# Relays.net
KiCad netlist of a schematic drawn in Altium Designer
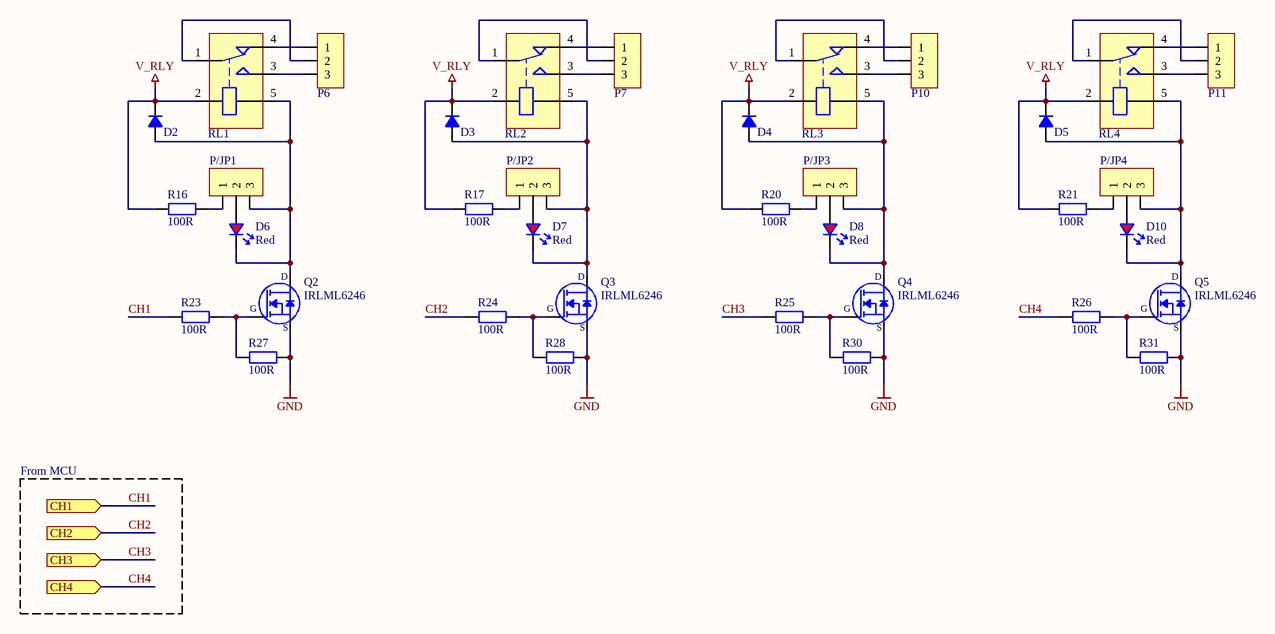
[diagram p0: Relays.SchDoc]

(export (version "E")
  (design (tool "Eeschema 10.0.6"))
  (components
    (comp (ref "D2")
      (value "D_SM")
      (footprint "AG.Passive:DO-214AC")
      (description "Generic Diode (Rectifier)")
      (libsource (lib "AG.Generic") (part "D_SM"))
    )
    (comp (ref "D3")
      (value "D_SM")
      (footprint "AG.Passive:DO-214AC")
      (description "Generic Diode (Rectifier)")
      (libsource (lib "AG.Generic") (part "D_SM"))
    )
    (comp (ref "D4")
      (value "D_SM")
      (footprint "AG.Passive:DO-214AC")
      (description "Generic Diode (Rectifier)")
      (libsource (lib "AG.Generic") (part "D_SM"))
    )
    (comp (ref "D5")
      (value "D_SM")
      (footprint "AG.Passive:DO-214AC")
      (description "Generic Diode (Rectifier)")
      (libsource (lib "AG.Generic") (part "D_SM"))
    )
    (comp (ref "D6")
      (value "Red")
      (footprint "AG.LED:LED1206")
      (description "Generic LED (Red)")
      (libsource (lib "AG.LED") (part "LED_RED"))
    )
    (comp (ref "D7")
      (value "Red")
      (footprint "AG.LED:LED1206")
      (description "Generic LED (Red)")
      (libsource (lib "AG.LED") (part "LED_RED"))
    )
    (comp (ref "D8")
      (value "Red")
      (footprint "AG.LED:LED1206")
      (description "Generic LED (Red)")
      (libsource (lib "AG.LED") (part "LED_RED"))
    )
    (comp (ref "D10")
      (value "Red")
      (footprint "AG.LED:LED1206")
      (description "Generic LED (Red)")
      (libsource (lib "AG.LED") (part "LED_RED"))
    )
    (comp (ref "P/JP1")
      (value "PINHDR_3x1")
      (footprint "AG.Connectors:HEADER-2.54-3P1")
      (description "Generic Pin Header 3x1")
      (libsource (lib "AG.Connectors") (part "PINHDR_3x1"))
    )
    (comp (ref "P/JP2")
      (value "PINHDR_3x1")
      (footprint "AG.Connectors:HEADER-2.54-3P1")
      (description "Generic Pin Header 3x1")
      (libsource (lib "AG.Connectors") (part "PINHDR_3x1"))
    )
    (comp (ref "P/JP3")
      (value "PINHDR_3x1")
      (footprint "AG.Connectors:HEADER-2.54-3P1")
      (description "Generic Pin Header 3x1")
      (libsource (lib "AG.Connectors") (part "PINHDR_3x1"))
    )
    (comp (ref "P/JP4")
      (value "PINHDR_3x1")
      (footprint "AG.Connectors:HEADER-2.54-3P1")
      (description "Generic Pin Header 3x1")
      (libsource (lib "AG.Connectors") (part "PINHDR_3x1"))
    )
    (comp (ref "P6")
      (value "ED500XDS-3")
      (footprint "AG.Connectors:ED500XDS-3")
      (description "TERM BLK 3P SIDE ENT 5.08MM PCB")
      (fields (field (name "PART NO") "EDZ500/3DS") (field (name "VOLTAGE") "300V"))
      (libsource (lib "AG.Connectors") (part "ED500XDS-3"))
    )
    (comp (ref "P7")
      (value "ED500XDS-3")
      (footprint "AG.Connectors:ED500XDS-3")
      (description "TERM BLK 3P SIDE ENT 5.08MM PCB")
      (fields (field (name "PART NO") "EDZ500/3DS") (field (name "VOLTAGE") "300V"))
      (libsource (lib "AG.Connectors") (part "ED500XDS-3"))
    )
    (comp (ref "P10")
      (value "ED500XDS-3")
      (footprint "AG.Connectors:ED500XDS-3")
      (description "TERM BLK 3P SIDE ENT 5.08MM PCB")
      (fields (field (name "PART NO") "EDZ500/3DS") (field (name "VOLTAGE") "300V"))
      (libsource (lib "AG.Connectors") (part "ED500XDS-3"))
    )
    (comp (ref "P11")
      (value "ED500XDS-3")
      (footprint "AG.Connectors:ED500XDS-3")
      (description "TERM BLK 3P SIDE ENT 5.08MM PCB")
      (fields (field (name "PART NO") "EDZ500/3DS") (field (name "VOLTAGE") "300V"))
      (libsource (lib "AG.Connectors") (part "ED500XDS-3"))
    )
    (comp (ref "Q2")
      (value "IRLML6246")
      (footprint "SOT-23-127P600-8N")
      (description "MOSFET N-CH 20V 4.1A SOT-23")
      (fields
        (field (name "PARTNO") "IRLML6246TRPBFCT-ND")
        (field (name "MANUFACTURER") "Infineon Technologies")
      )
      (libsource (lib "AG") (part "IRLML6246TRPBF"))
    )
    (comp (ref "Q3")
      (value "IRLML6246")
      (footprint "SOT-23-127P600-8N")
      (description "MOSFET N-CH 20V 4.1A SOT-23")
      (fields
        (field (name "PARTNO") "IRLML6246TRPBFCT-ND")
        (field (name "MANUFACTURER") "Infineon Technologies")
      )
      (libsource (lib "AG") (part "IRLML6246TRPBF"))
    )
    (comp (ref "Q4")
      (value "IRLML6246")
      (footprint "SOT-23-127P600-8N")
      (description "MOSFET N-CH 20V 4.1A SOT-23")
      (fields
        (field (name "PARTNO") "IRLML6246TRPBFCT-ND")
        (field (name "MANUFACTURER") "Infineon Technologies")
      )
      (libsource (lib "AG") (part "IRLML6246TRPBF"))
    )
    (comp (ref "Q5")
      (value "IRLML6246")
      (footprint "SOT-23-127P600-8N")
      (description "MOSFET N-CH 20V 4.1A SOT-23")
      (fields
        (field (name "PARTNO") "IRLML6246TRPBFCT-ND")
        (field (name "MANUFACTURER") "Infineon Technologies")
      )
      (libsource (lib "AG") (part "IRLML6246TRPBF"))
    )
    (comp (ref "R16")
      (value "100R")
      (footprint "AG.Passive:R0805")
      (description "Generic Resistor")
      (fields (field (name "TOLERANCE") "1%"))
      (libsource (lib "AG.Generic") (part "R"))
    )
    (comp (ref "R17")
      (value "100R")
      (footprint "AG.Passive:R0805")
      (description "Generic Resistor")
      (fields (field (name "TOLERANCE") "1%"))
      (libsource (lib "AG.Generic") (part "R"))
    )
    (comp (ref "R20")
      (value "100R")
      (footprint "AG.Passive:R0805")
      (description "Generic Resistor")
      (fields (field (name "TOLERANCE") "1%"))
      (libsource (lib "AG.Generic") (part "R"))
    )
    (comp (ref "R21")
      (value "100R")
      (footprint "AG.Passive:R0805")
      (description "Generic Resistor")
      (fields (field (name "TOLERANCE") "1%"))
      (libsource (lib "AG.Generic") (part "R"))
    )
    (comp (ref "R23")
      (value "100R")
      (footprint "AG.Passive:R0805")
      (description "Generic Resistor")
      (fields (field (name "TOLERANCE") "1%"))
      (libsource (lib "AG.Generic") (part "R"))
    )
    (comp (ref "R24")
      (value "100R")
      (footprint "AG.Passive:R0805")
      (description "Generic Resistor")
      (fields (field (name "TOLERANCE") "1%"))
      (libsource (lib "AG.Generic") (part "R"))
    )
    (comp (ref "R25")
      (value "100R")
      (footprint "AG.Passive:R0805")
      (description "Generic Resistor")
      (fields (field (name "TOLERANCE") "1%"))
      (libsource (lib "AG.Generic") (part "R"))
    )
    (comp (ref "R26")
      (value "100R")
      (footprint "AG.Passive:R0805")
      (description "Generic Resistor")
      (fields (field (name "TOLERANCE") "1%"))
      (libsource (lib "AG.Generic") (part "R"))
    )
    (comp (ref "R27")
      (value "100R")
      (footprint "AG.Passive:R0805")
      (description "Generic Resistor")
      (fields (field (name "TOLERANCE") "1%"))
      (libsource (lib "AG.Generic") (part "R"))
    )
    (comp (ref "R28")
      (value "100R")
      (footprint "AG.Passive:R0805")
      (description "Generic Resistor")
      (fields (field (name "TOLERANCE") "1%"))
      (libsource (lib "AG.Generic") (part "R"))
    )
    (comp (ref "R30")
      (value "100R")
      (footprint "AG.Passive:R0805")
      (description "Generic Resistor")
      (fields (field (name "TOLERANCE") "1%"))
      (libsource (lib "AG.Generic") (part "R"))
    )
    (comp (ref "R31")
      (value "100R")
      (footprint "AG.Passive:R0805")
      (description "Generic Resistor")
      (fields (field (name "TOLERANCE") "1%"))
      (libsource (lib "AG.Generic") (part "R"))
    )
    (comp (ref "RL1")
      (value "*")
      (footprint "AG.Relays:SRD-VDC-SL-C")
      (description "General Purpose Power Relay SPDT (1 Form C)")
      (libsource (lib "AG.Misc") (part "RELAY-SPDT"))
    )
    (comp (ref "RL2")
      (value "*")
      (footprint "AG.Relays:SRD-VDC-SL-C")
      (description "General Purpose Power Relay SPDT (1 Form C)")
      (libsource (lib "AG.Misc") (part "RELAY-SPDT"))
    )
    (comp (ref "RL3")
      (value "*")
      (footprint "AG.Relays:SRD-VDC-SL-C")
      (description "General Purpose Power Relay SPDT (1 Form C)")
      (libsource (lib "AG.Misc") (part "RELAY-SPDT"))
    )
    (comp (ref "RL4")
      (value "*")
      (footprint "AG.Relays:SRD-VDC-SL-C")
      (description "General Purpose Power Relay SPDT (1 Form C)")
      (libsource (lib "AG.Misc") (part "RELAY-SPDT"))
    )
  )
  (nets
    (net (code "1") (name "/CH1") (class "Default") (node (ref "R23") (pin "2") (pintype "passive")))
    (net (code "2") (name "/CH2") (class "Default") (node (ref "R24") (pin "2") (pintype "passive")))
    (net (code "3") (name "/CH3") (class "Default") (node (ref "R25") (pin "2") (pintype "passive")))
    (net (code "4") (name "/CH4") (class "Default") (node (ref "R26") (pin "2") (pintype "passive")))
    (net (code "5") (name "GND") (class "Default")
      (node (ref "Q2") (pin "2") (pinfunction "S_2") (pintype "passive"))
      (node (ref "Q3") (pin "2") (pinfunction "S_2") (pintype "passive"))
      (node (ref "Q4") (pin "2") (pinfunction "S_2") (pintype "passive"))
      (node (ref "Q5") (pin "2") (pinfunction "S_2") (pintype "passive"))
      (node (ref "R27") (pin "1") (pintype "passive"))
      (node (ref "R28") (pin "1") (pintype "passive"))
      (node (ref "R30") (pin "1") (pintype "passive"))
      (node (ref "R31") (pin "1") (pintype "passive"))
    )
    (net (code "6") (name "Net-(D2-A)") (class "Default")
      (node (ref "D2") (pin "1") (pinfunction "A_1") (pintype "passive"))
      (node (ref "D6") (pin "2") (pinfunction "C_2") (pintype "passive"))
      (node (ref "P/JP1") (pin "3") (pinfunction "3_3") (pintype "passive"))
      (node (ref "Q2") (pin "3") (pinfunction "D_3") (pintype "passive"))
      (node (ref "RL1") (pin "5") (pinfunction "SW1_5") (pintype "passive"))
    )
    (net (code "7") (name "Net-(D3-A)") (class "Default")
      (node (ref "D3") (pin "1") (pinfunction "A_1") (pintype "passive"))
      (node (ref "D7") (pin "2") (pinfunction "C_2") (pintype "passive"))
      (node (ref "P/JP2") (pin "3") (pinfunction "3_3") (pintype "passive"))
      (node (ref "Q3") (pin "3") (pinfunction "D_3") (pintype "passive"))
      (node (ref "RL2") (pin "5") (pinfunction "SW1_5") (pintype "passive"))
    )
    (net (code "8") (name "Net-(D4-A)") (class "Default")
      (node (ref "D4") (pin "1") (pinfunction "A_1") (pintype "passive"))
      (node (ref "D8") (pin "2") (pinfunction "C_2") (pintype "passive"))
      (node (ref "P/JP3") (pin "3") (pinfunction "3_3") (pintype "passive"))
      (node (ref "Q4") (pin "3") (pinfunction "D_3") (pintype "passive"))
      (node (ref "RL3") (pin "5") (pinfunction "SW1_5") (pintype "passive"))
    )
    (net (code "9") (name "Net-(D6-A)") (class "Default")
      (node (ref "D6") (pin "1") (pinfunction "A_1") (pintype "passive"))
      (node (ref "P/JP1") (pin "2") (pinfunction "2_2") (pintype "passive"))
    )
    (net (code "10") (name "Net-(D7-A)") (class "Default")
      (node (ref "D7") (pin "1") (pinfunction "A_1") (pintype "passive"))
      (node (ref "P/JP2") (pin "2") (pinfunction "2_2") (pintype "passive"))
    )
    (net (code "11") (name "Net-(D8-A)") (class "Default")
      (node (ref "D8") (pin "1") (pinfunction "A_1") (pintype "passive"))
      (node (ref "P/JP3") (pin "2") (pinfunction "2_2") (pintype "passive"))
    )
    (net (code "12") (name "Net-(D10-A)") (class "Default")
      (node (ref "D10") (pin "1") (pinfunction "A_1") (pintype "passive"))
      (node (ref "P/JP4") (pin "2") (pinfunction "2_2") (pintype "passive"))
    )
    (net (code "13") (name "Net-(D10-C)") (class "Default")
      (node (ref "D10") (pin "2") (pinfunction "C_2") (pintype "passive"))
      (node (ref "D5") (pin "1") (pinfunction "A_1") (pintype "passive"))
      (node (ref "P/JP4") (pin "3") (pinfunction "3_3") (pintype "passive"))
      (node (ref "Q5") (pin "3") (pinfunction "D_3") (pintype "passive"))
      (node (ref "RL4") (pin "5") (pinfunction "SW1_5") (pintype "passive"))
    )
    (net (code "14") (name "Net-(P/JP1-Pad1)") (class "Default")
      (node (ref "P/JP1") (pin "1") (pinfunction "1_1") (pintype "passive"))
      (node (ref "R16") (pin "1") (pintype "passive"))
    )
    (net (code "15") (name "Net-(P/JP2-Pad1)") (class "Default")
      (node (ref "P/JP2") (pin "1") (pinfunction "1_1") (pintype "passive"))
      (node (ref "R17") (pin "1") (pintype "passive"))
    )
    (net (code "16") (name "Net-(P/JP3-Pad1)") (class "Default")
      (node (ref "P/JP3") (pin "1") (pinfunction "1_1") (pintype "passive"))
      (node (ref "R20") (pin "1") (pintype "passive"))
    )
    (net (code "17") (name "Net-(P/JP4-Pad1)") (class "Default")
      (node (ref "P/JP4") (pin "1") (pinfunction "1_1") (pintype "passive"))
      (node (ref "R21") (pin "1") (pintype "passive"))
    )
    (net (code "18") (name "Net-(Q2-G)") (class "Default")
      (node (ref "Q2") (pin "1") (pinfunction "G_1") (pintype "passive"))
      (node (ref "R23") (pin "1") (pintype "passive"))
      (node (ref "R27") (pin "2") (pintype "passive"))
    )
    (net (code "19") (name "Net-(Q3-G)") (class "Default")
      (node (ref "Q3") (pin "1") (pinfunction "G_1") (pintype "passive"))
      (node (ref "R24") (pin "1") (pintype "passive"))
      (node (ref "R28") (pin "2") (pintype "passive"))
    )
    (net (code "20") (name "Net-(Q4-G)") (class "Default")
      (node (ref "Q4") (pin "1") (pinfunction "G_1") (pintype "passive"))
      (node (ref "R25") (pin "1") (pintype "passive"))
      (node (ref "R30") (pin "2") (pintype "passive"))
    )
    (net (code "21") (name "Net-(Q5-G)") (class "Default")
      (node (ref "Q5") (pin "1") (pinfunction "G_1") (pintype "passive"))
      (node (ref "R26") (pin "1") (pintype "passive"))
      (node (ref "R31") (pin "2") (pintype "passive"))
    )
    (net (code "22") (name "Net-(RL1-COM)") (class "Default")
      (node (ref "P6") (pin "2") (pinfunction "2_2") (pintype "passive"))
      (node (ref "RL1") (pin "1") (pinfunction "COM_1") (pintype "passive"))
    )
    (net (code "23") (name "Net-(RL1-NC)") (class "Default")
      (node (ref "P6") (pin "1") (pinfunction "1_1") (pintype "passive"))
      (node (ref "RL1") (pin "4") (pinfunction "NC_4") (pintype "passive"))
    )
    (net (code "24") (name "Net-(RL1-NO)") (class "Default")
      (node (ref "P6") (pin "3") (pinfunction "3_3") (pintype "passive"))
      (node (ref "RL1") (pin "3") (pinfunction "NO_3") (pintype "passive"))
    )
    (net (code "25") (name "Net-(RL2-COM)") (class "Default")
      (node (ref "P7") (pin "2") (pinfunction "2_2") (pintype "passive"))
      (node (ref "RL2") (pin "1") (pinfunction "COM_1") (pintype "passive"))
    )
    (net (code "26") (name "Net-(RL2-NC)") (class "Default")
      (node (ref "P7") (pin "1") (pinfunction "1_1") (pintype "passive"))
      (node (ref "RL2") (pin "4") (pinfunction "NC_4") (pintype "passive"))
    )
    (net (code "27") (name "Net-(RL2-NO)") (class "Default")
      (node (ref "P7") (pin "3") (pinfunction "3_3") (pintype "passive"))
      (node (ref "RL2") (pin "3") (pinfunction "NO_3") (pintype "passive"))
    )
    (net (code "28") (name "Net-(RL3-COM)") (class "Default")
      (node (ref "P10") (pin "2") (pinfunction "2_2") (pintype "passive"))
      (node (ref "RL3") (pin "1") (pinfunction "COM_1") (pintype "passive"))
    )
    (net (code "29") (name "Net-(RL3-NC)") (class "Default")
      (node (ref "P10") (pin "1") (pinfunction "1_1") (pintype "passive"))
      (node (ref "RL3") (pin "4") (pinfunction "NC_4") (pintype "passive"))
    )
    (net (code "30") (name "Net-(RL3-NO)") (class "Default")
      (node (ref "P10") (pin "3") (pinfunction "3_3") (pintype "passive"))
      (node (ref "RL3") (pin "3") (pinfunction "NO_3") (pintype "passive"))
    )
    (net (code "31") (name "Net-(RL4-COM)") (class "Default")
      (node (ref "P11") (pin "2") (pinfunction "2_2") (pintype "passive"))
      (node (ref "RL4") (pin "1") (pinfunction "COM_1") (pintype "passive"))
    )
    (net (code "32") (name "Net-(RL4-NC)") (class "Default")
      (node (ref "P11") (pin "1") (pinfunction "1_1") (pintype "passive"))
      (node (ref "RL4") (pin "4") (pinfunction "NC_4") (pintype "passive"))
    )
    (net (code "33") (name "Net-(RL4-NO)") (class "Default")
      (node (ref "P11") (pin "3") (pinfunction "3_3") (pintype "passive"))
      (node (ref "RL4") (pin "3") (pinfunction "NO_3") (pintype "passive"))
    )
    (net (code "34") (name "V_RLY") (class "Default")
      (node (ref "D2") (pin "2") (pinfunction "C_2") (pintype "passive"))
      (node (ref "D3") (pin "2") (pinfunction "C_2") (pintype "passive"))
      (node (ref "D4") (pin "2") (pinfunction "C_2") (pintype "passive"))
      (node (ref "D5") (pin "2") (pinfunction "C_2") (pintype "passive"))
      (node (ref "R16") (pin "2") (pintype "passive"))
      (node (ref "R17") (pin "2") (pintype "passive"))
      (node (ref "R20") (pin "2") (pintype "passive"))
      (node (ref "R21") (pin "2") (pintype "passive"))
      (node (ref "RL1") (pin "2") (pinfunction "SW2_2") (pintype "passive"))
      (node (ref "RL2") (pin "2") (pinfunction "SW2_2") (pintype "passive"))
      (node (ref "RL3") (pin "2") (pinfunction "SW2_2") (pintype "passive"))
      (node (ref "RL4") (pin "2") (pinfunction "SW2_2") (pintype "passive"))
    )
  )
)
